# Battery_Measurement.net
KiCad netlist of a schematic drawn in Altium Designer
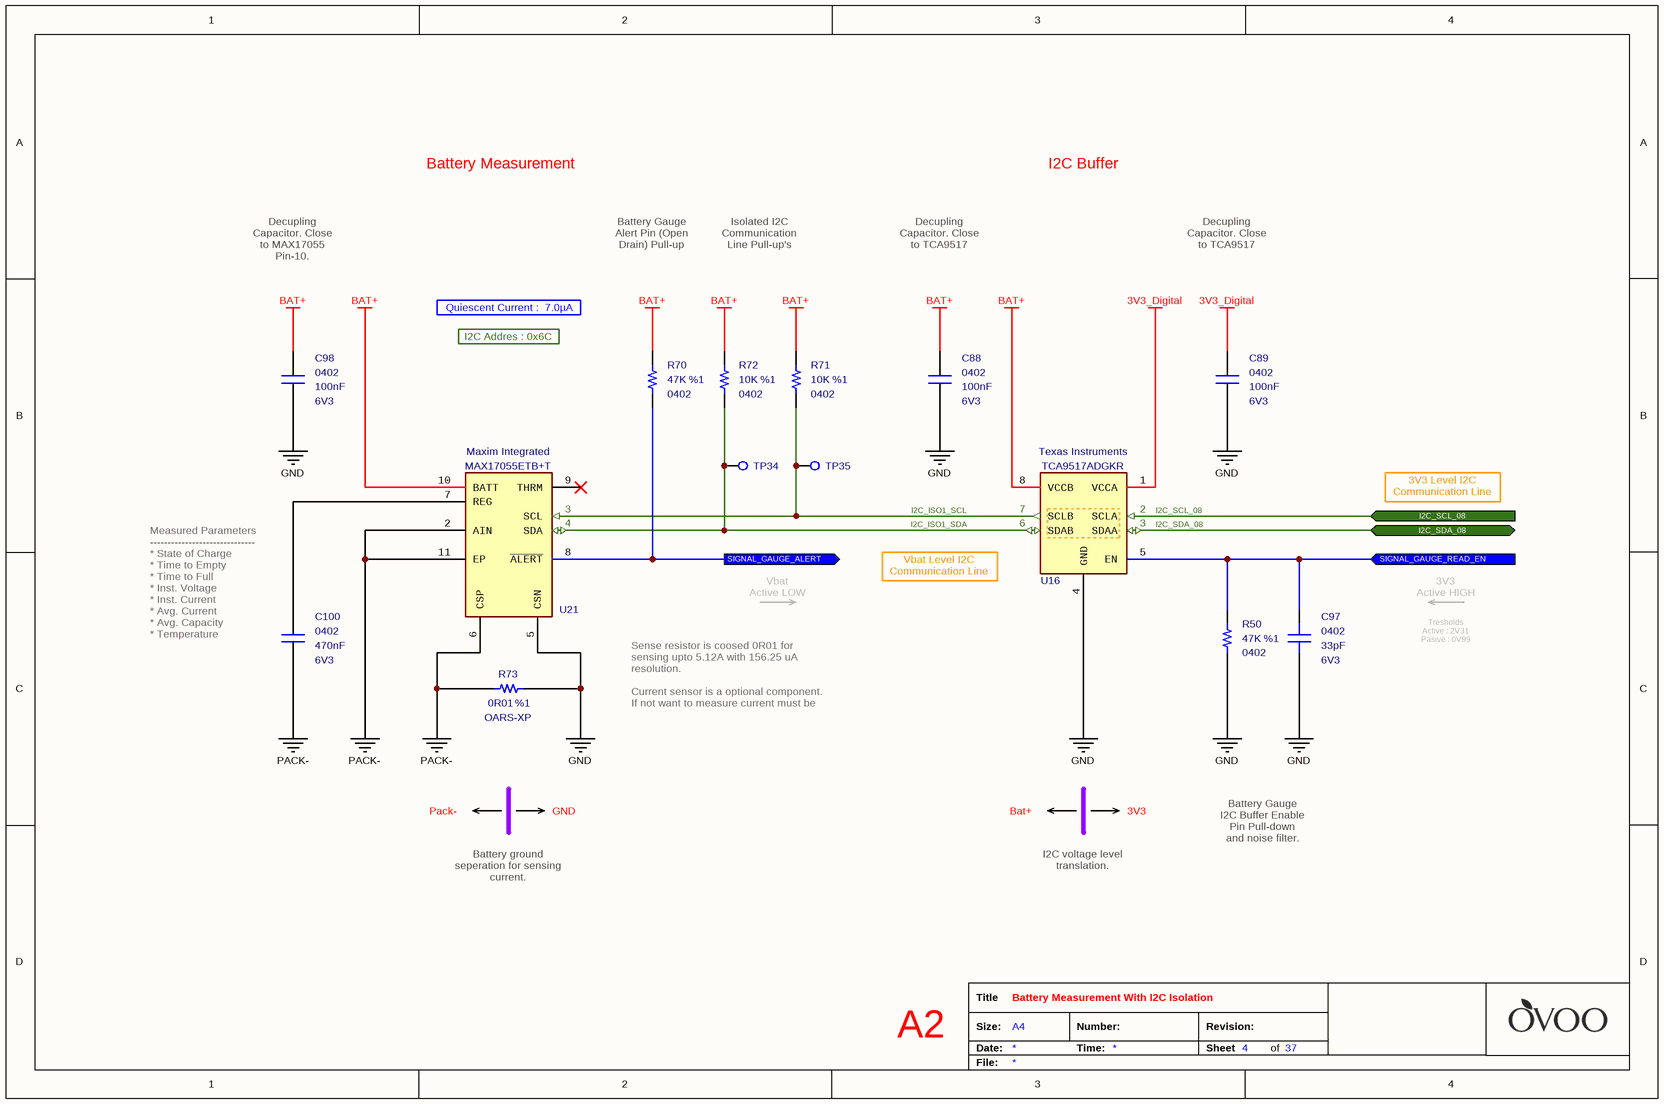
[diagram p0: Battery Measurement.SchDoc]

(export (version "E")
  (design (tool "Eeschema 10.0.6"))
  (components
    (comp (ref "C88")
      (value "100nF")
      (footprint "CAPACITOR_0402")
      (description "Capacitor - 100nF [0402-6V3] (Ceramic)")
      (fields
        (field (name "MANUFACTURER_PART_NUMBER") "04026D104KAT4A")
        (field (name "MOUSER_PART_NUMBER") "581-04026D104KAT4A")
        (field (name "CASE") "0402")
        (field (name "VOLTAGE") "6V3")
      )
      (libsource (lib "Ovoo_Schematic") (part "Capacitor - 100nF [0402-6V3]"))
    )
    (comp (ref "C89")
      (value "100nF")
      (footprint "CAPACITOR_0402")
      (description "Capacitor - 100nF [0402-6V3] (Ceramic)")
      (fields
        (field (name "MANUFACTURER_PART_NUMBER") "04026D104KAT4A")
        (field (name "MOUSER_PART_NUMBER") "581-04026D104KAT4A")
        (field (name "CASE") "0402")
        (field (name "VOLTAGE") "6V3")
      )
      (libsource (lib "Ovoo_Schematic") (part "Capacitor - 100nF [0402-6V3]"))
    )
    (comp (ref "C97")
      (value "33pF")
      (footprint "CAPACITOR_0402")
      (description "Capacitor - 33pF [0402] (Ceramic)")
      (fields
        (field (name "MANUFACTURER_PART_NUMBER") "C0402C330J9RACAUTO")
        (field (name "MOUSER_PART_NUMBER") "80-C0402C330J9RAUTO")
        (field (name "CASE") "0402")
        (field (name "VOLTAGE") "6V3")
      )
      (libsource (lib "Ovoo_Schematic") (part "Capacitor - 33pF [0402-6V3]"))
    )
    (comp (ref "C98")
      (value "100nF")
      (footprint "CAPACITOR_0402")
      (description "Capacitor - 100nF [0402-6V3] (Ceramic)")
      (fields
        (field (name "MANUFACTURER_PART_NUMBER") "04026D104KAT4A")
        (field (name "MOUSER_PART_NUMBER") "581-04026D104KAT4A")
        (field (name "CASE") "0402")
        (field (name "VOLTAGE") "6V3")
      )
      (libsource (lib "Ovoo_Schematic") (part "Capacitor - 100nF [0402-6V3]"))
    )
    (comp (ref "C100")
      (value "470nF")
      (footprint "CAPACITOR_0402")
      (description "Capacitor - 470nF [0402] (Ceramic)")
      (fields
        (field (name "MANUFACTURER_PART_NUMBER") "04026C474KAT2A")
        (field (name "MOUSER_PART_NUMBER") "581-04026C474KAT2A")
        (field (name "CASE") "0402")
        (field (name "VOLTAGE") "6V3")
      )
      (libsource (lib "Ovoo_Schematic") (part "Capacitor - 470nF [0402-6V3]"))
    )
    (comp (ref "R50")
      (value "47K")
      (footprint "RESISTOR_0402")
      (description "Thick Film Resistors - SMD 1/16 W 47 Kohms 1%")
      (fields
        (field (name "MANUFACTURER_PART_NUMBER") "CRCW040247K0FKED")
        (field (name "MOUSER_PART_NUMBER") "71-CRCW0402-47K-E3")
        (field (name "TOLERANCE") "%1")
        (field (name "CASE") "0402")
      )
      (libsource (lib "Ovoo_Schematic") (part "Resistor - 47K"))
    )
    (comp (ref "R70")
      (value "47K")
      (footprint "RESISTOR_0402")
      (description "Thick Film Resistors - SMD 1/16 W 47 Kohms 1%")
      (fields
        (field (name "MANUFACTURER_PART_NUMBER") "CRCW040247K0FKED")
        (field (name "MOUSER_PART_NUMBER") "71-CRCW0402-47K-E3")
        (field (name "TOLERANCE") "%1")
        (field (name "CASE") "0402")
      )
      (libsource (lib "Ovoo_Schematic") (part "Resistor - 47K"))
    )
    (comp (ref "R71")
      (value "10K")
      (footprint "RESISTOR_0402")
      (description "Thick Film Resistors - SMD 1/16 W 10 Kohms 1%")
      (fields
        (field (name "MANUFACTURER_PART_NUMBER") "CRCW040210K0FKED")
        (field (name "MOUSER_PART_NUMBER") "71-CRCW0402-10K-E3")
        (field (name "TOLERANCE") "%1")
        (field (name "CASE") "0402")
      )
      (libsource (lib "Ovoo_Schematic") (part "Resistor - 10K"))
    )
    (comp (ref "R72")
      (value "10K")
      (footprint "RESISTOR_0402")
      (description "Thick Film Resistors - SMD 1/16 W 10 Kohms 1%")
      (fields
        (field (name "MANUFACTURER_PART_NUMBER") "CRCW040210K0FKED")
        (field (name "MOUSER_PART_NUMBER") "71-CRCW0402-10K-E3")
        (field (name "TOLERANCE") "%1")
        (field (name "CASE") "0402")
      )
      (libsource (lib "Ovoo_Schematic") (part "Resistor - 10K"))
    )
    (comp (ref "R73")
      (value "0R01")
      (footprint "RESISTOR_OARSXP")
      (description "Current Sense Resistors - SMD 10 W 0.01 ohms 1%")
      (fields
        (field (name "MANUFACTURER_PART_NUMBER") "OARSXPR010FLF")
        (field (name "MOUSER_PART_NUMBER") "66-OARSXPR010FLF")
        (field (name "CASE") "OARS-XP")
        (field (name "TOLERANCE") "%1")
      )
      (libsource (lib "Ovoo_Schematic") (part "Resistor - 0R01 (Current Sense)"))
    )
    (comp (ref "TP34")
      (value "PCB - Test Point")
      (footprint "Test_Pad - Hole")
      (description "Test Point")
      (libsource (lib "Ovoo_Schematic") (part "PCB - Test Point"))
    )
    (comp (ref "TP35")
      (value "PCB - Test Point")
      (footprint "Test_Pad - Hole")
      (description "Test Point")
      (libsource (lib "Ovoo_Schematic") (part "PCB - Test Point"))
    )
    (comp (ref "U16")
      (value "I2C Bus Repeater")
      (footprint "MSOP-8-4")
      (description "Interface - Signal Buffers, Repeaters Level-Translting I2C Bus Repeater")
      (fields
        (field (name "MANUFACTURER_NAME") "Texas Instruments")
        (field (name "MANUFACTURER_PART_NUMBER") "TCA9517ADGKR")
        (field (name "MOUSER PART NUMBER") "595-TCA9517ADGKR")
      )
      (libsource (lib "Ovoo_Schematic") (part "IC - TCA9517ADGKR"))
    )
    (comp (ref "U21")
      (value "Battery Gauge")
      (footprint "TDFN-10")
      (description "Battery Management Stand-Alone ModelGauge m5 Fuel Gauge")
      (fields
        (field (name "MOUSER_PART_NUMBER") "700-MAX17055ETB+T")
        (field (name "MANUFACTURER_PART_NUMBER") "MAX17055ETB+T")
        (field (name "MANUFACTURER_NAME") "Maxim Integrated")
      )
      (libsource (lib "Ovoo_Schematic") (part "IC - MAX17055ETB+T"))
    )
  )
  (nets
    (net (code "1") (name "/I2C_ISO1_SCL") (class "Default")
      (node (ref "R71") (pin "1") (pinfunction "1_1") (pintype "passive"))
      (node (ref "TP35") (pin "1") (pinfunction "TP_1") (pintype "passive"))
      (node (ref "U16") (pin "7") (pinfunction "SCLB_7") (pintype "output"))
      (node (ref "U21") (pin "3") (pinfunction "SCL_3") (pintype "input"))
    )
    (net (code "2") (name "/I2C_ISO1_SDA") (class "Default")
      (node (ref "R72") (pin "1") (pinfunction "1_1") (pintype "passive"))
      (node (ref "TP34") (pin "1") (pinfunction "TP_1") (pintype "passive"))
      (node (ref "U16") (pin "6") (pinfunction "SDAB_6") (pintype "bidirectional"))
      (node (ref "U21") (pin "4") (pinfunction "SDA_4") (pintype "bidirectional"))
    )
    (net (code "3") (name "/I2C_SCL_08") (class "Default")
      (node (ref "U16") (pin "2") (pinfunction "SCLA_2") (pintype "input"))
    )
    (net (code "4") (name "/I2C_SDA_08") (class "Default")
      (node (ref "U16") (pin "3") (pinfunction "SDAA_3") (pintype "bidirectional"))
    )
    (net (code "5") (name "/SIGNAL_GAUGE_ALERT") (class "Default")
      (node (ref "R70") (pin "1") (pinfunction "1_1") (pintype "passive"))
      (node (ref "U21") (pin "8") (pinfunction "~{ALERT}_8") (pintype "open_collector"))
    )
    (net (code "6") (name "/SIGNAL_GAUGE_READ_EN") (class "Default")
      (node (ref "C97") (pin "2") (pinfunction "2_2") (pintype "passive"))
      (node (ref "R50") (pin "2") (pinfunction "2_2") (pintype "passive"))
      (node (ref "U16") (pin "5") (pinfunction "EN_5") (pintype "passive"))
    )
    (net (code "7") (name "3V3_Digital") (class "Default")
      (node (ref "C89") (pin "1") (pinfunction "1_1") (pintype "passive"))
      (node (ref "U16") (pin "1") (pinfunction "VCCA_1") (pintype "power_in"))
    )
    (net (code "8") (name "BAT+") (class "Default")
      (node (ref "C88") (pin "1") (pinfunction "1_1") (pintype "passive"))
      (node (ref "C98") (pin "1") (pinfunction "1_1") (pintype "passive"))
      (node (ref "R70") (pin "2") (pinfunction "2_2") (pintype "passive"))
      (node (ref "R71") (pin "2") (pinfunction "2_2") (pintype "passive"))
      (node (ref "R72") (pin "2") (pinfunction "2_2") (pintype "passive"))
      (node (ref "U16") (pin "8") (pinfunction "VCCB_8") (pintype "power_in"))
      (node (ref "U21") (pin "10") (pinfunction "BATT_10") (pintype "power_in"))
    )
    (net (code "9") (name "GND") (class "Default")
      (node (ref "C88") (pin "2") (pinfunction "2_2") (pintype "passive"))
      (node (ref "C89") (pin "2") (pinfunction "2_2") (pintype "passive"))
      (node (ref "C97") (pin "1") (pinfunction "1_1") (pintype "passive"))
      (node (ref "C98") (pin "2") (pinfunction "2_2") (pintype "passive"))
      (node (ref "R50") (pin "1") (pinfunction "1_1") (pintype "passive"))
      (node (ref "R73") (pin "1") (pinfunction "1_1") (pintype "passive"))
      (node (ref "U16") (pin "4") (pinfunction "GND_4") (pintype "power_in"))
      (node (ref "U21") (pin "5") (pinfunction "CSN_5") (pintype "power_in"))
    )
    (net (code "10") (name "Net-(U21-REG)") (class "Default")
      (node (ref "C100") (pin "2") (pinfunction "2_2") (pintype "passive"))
      (node (ref "U21") (pin "7") (pinfunction "REG_7") (pintype "passive"))
    )
    (net (code "11") (name "PACK-") (class "Default")
      (node (ref "C100") (pin "1") (pinfunction "1_1") (pintype "passive"))
      (node (ref "R73") (pin "2") (pinfunction "2_2") (pintype "passive"))
      (node (ref "U21") (pin "11") (pinfunction "EP_11") (pintype "passive"))
      (node (ref "U21") (pin "2") (pinfunction "AIN_2") (pintype "passive"))
      (node (ref "U21") (pin "6") (pinfunction "CSP_6") (pintype "power_in"))
    )
    (net (code "12") (name "unconnected-(U21-THRM-Pad9)") (class "Default")
      (node (ref "U21") (pin "9") (pinfunction "THRM_9") (pintype "passive+no_connect"))
    )
  )
)
